# fpc.net
KiCad netlist of a schematic drawn in EAGLE
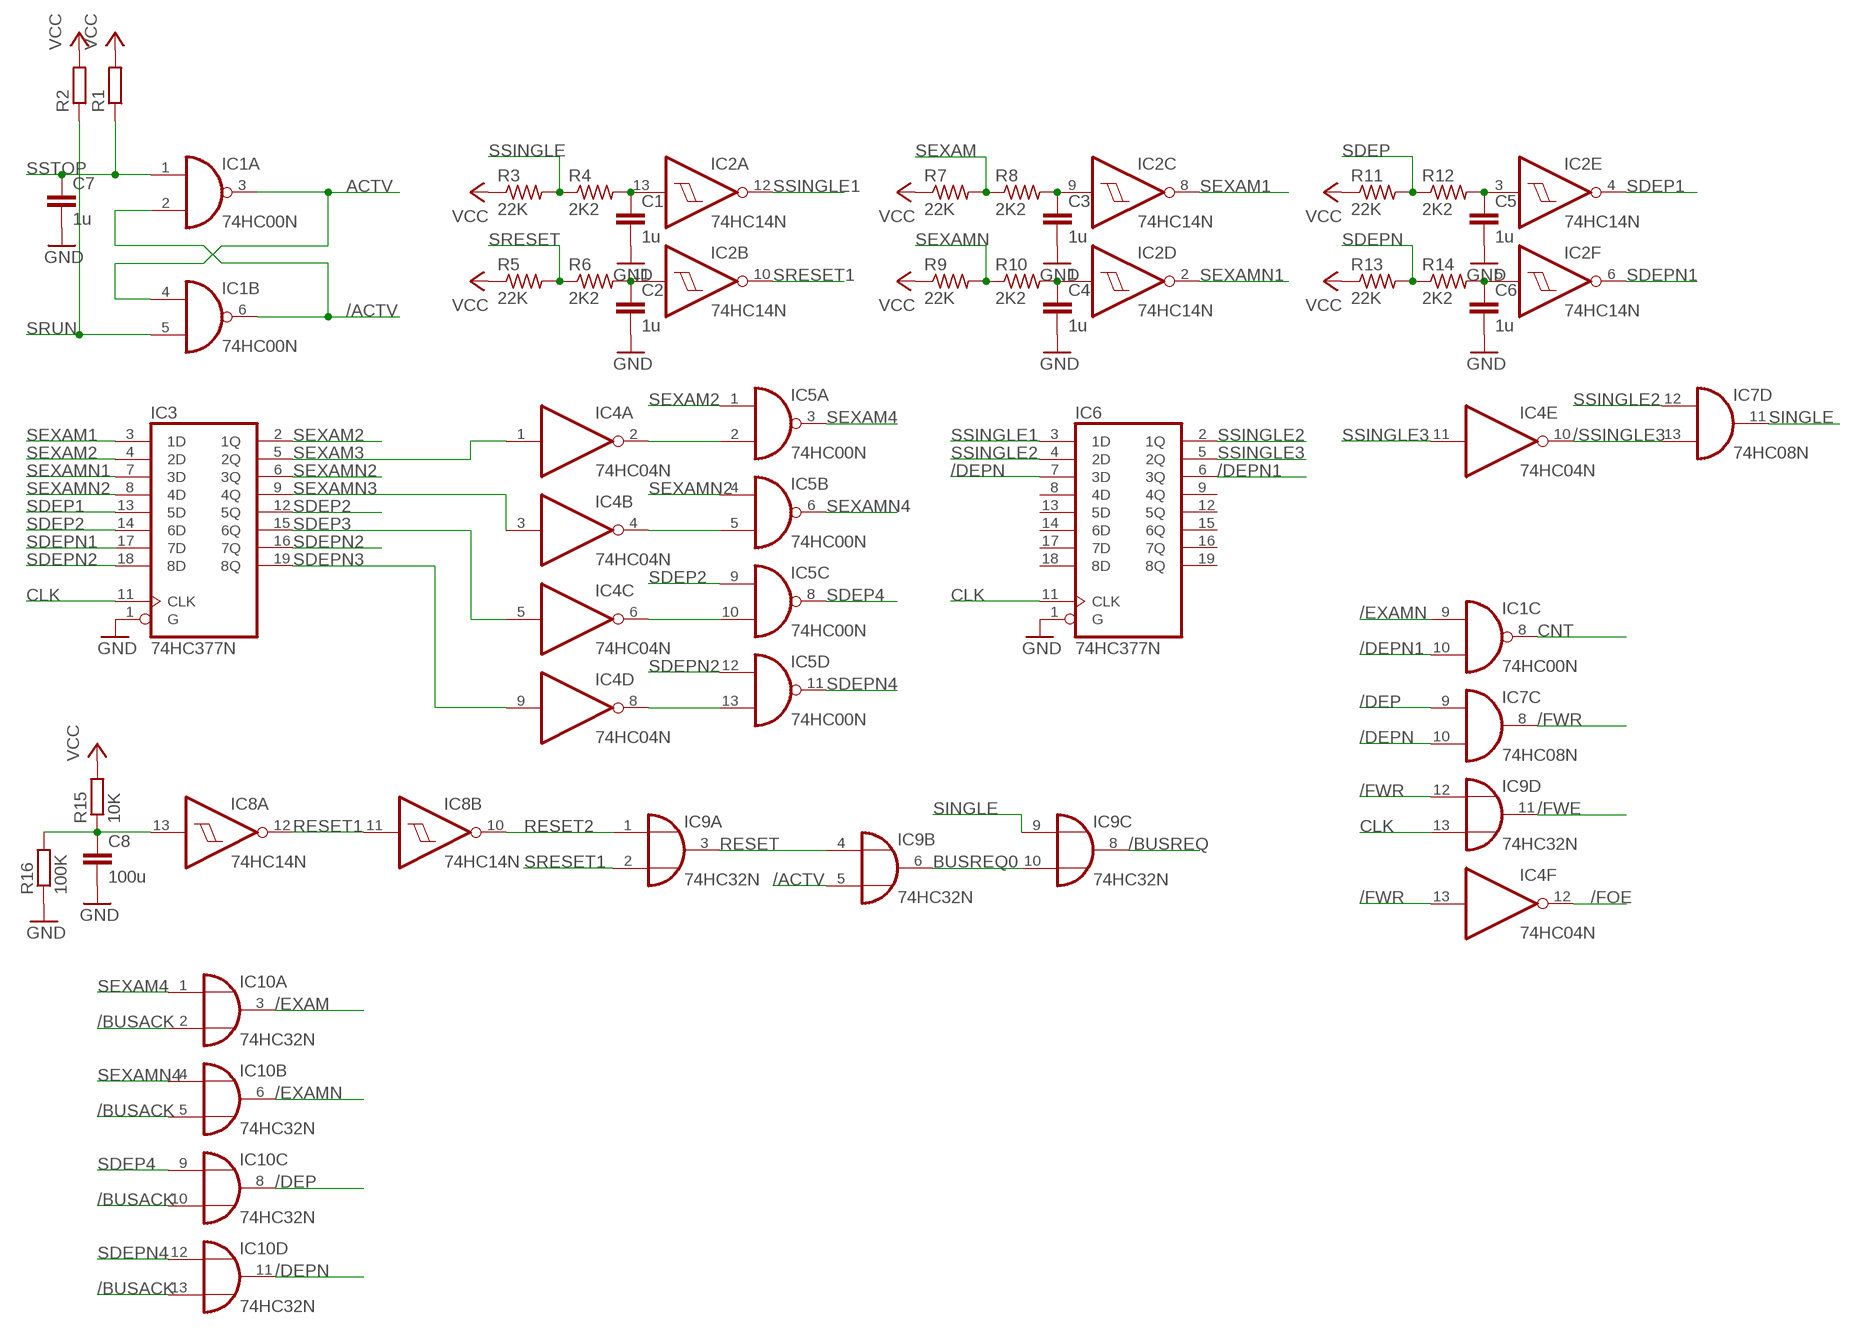
[diagram p0: schematic, sheet 1]

(export (version "E")
  (design (tool "Eeschema 10.0.6"))
  (components
    (comp (ref "C1")
      (value "1u")
      (footprint "eagle-import:C025-025X050")
      (libsource (lib "eagle-import") (part "C-EU025-025X050"))
    )
    (comp (ref "C2")
      (value "1u")
      (footprint "eagle-import:C025-025X050")
      (libsource (lib "eagle-import") (part "C-EU025-025X050"))
    )
    (comp (ref "C3")
      (value "1u")
      (footprint "eagle-import:C025-025X050")
      (libsource (lib "eagle-import") (part "C-EU025-025X050"))
    )
    (comp (ref "C4")
      (value "1u")
      (footprint "eagle-import:C025-025X050")
      (libsource (lib "eagle-import") (part "C-EU025-025X050"))
    )
    (comp (ref "C5")
      (value "1u")
      (footprint "eagle-import:C025-025X050")
      (libsource (lib "eagle-import") (part "C-EU025-025X050"))
    )
    (comp (ref "C6")
      (value "1u")
      (footprint "eagle-import:C025-025X050")
      (libsource (lib "eagle-import") (part "C-EU025-025X050"))
    )
    (comp (ref "C7")
      (value "1u")
      (footprint "eagle-import:C025-025X050")
      (libsource (lib "eagle-import") (part "C-EU025-025X050"))
    )
    (comp (ref "C8")
      (value "100u")
      (footprint "eagle-import:C025-025X050")
      (libsource (lib "eagle-import") (part "C-EU025-025X050"))
    )
    (comp (ref "IC1")
      (value "74HC00N")
      (footprint "eagle-import:DIL14")
      (libsource (lib "eagle-import") (part "7400NHC"))
    )
    (comp (ref "IC2")
      (value "74HC14N")
      (footprint "eagle-import:DIL14")
      (libsource (lib "eagle-import") (part "7414NHC"))
    )
    (comp (ref "IC3")
      (value "74HC377N")
      (footprint "eagle-import:DIL20")
      (libsource (lib "eagle-import") (part "74377NHC"))
    )
    (comp (ref "IC4")
      (value "74HC04N")
      (footprint "eagle-import:DIL14")
      (libsource (lib "eagle-import") (part "7404NHC"))
    )
    (comp (ref "IC5")
      (value "74HC00N")
      (footprint "eagle-import:DIL14")
      (libsource (lib "eagle-import") (part "7400NHC"))
    )
    (comp (ref "IC6")
      (value "74HC377N")
      (footprint "eagle-import:DIL20")
      (libsource (lib "eagle-import") (part "74377NHC"))
    )
    (comp (ref "IC7")
      (value "74HC08N")
      (footprint "eagle-import:DIL14")
      (libsource (lib "eagle-import") (part "7408NHC"))
    )
    (comp (ref "IC8")
      (value "74HC14N")
      (footprint "eagle-import:DIL14")
      (libsource (lib "eagle-import") (part "7414NHC"))
    )
    (comp (ref "IC9")
      (value "74HC32N")
      (footprint "eagle-import:DIL14")
      (libsource (lib "eagle-import") (part "7432NHC"))
    )
    (comp (ref "IC10")
      (value "74HC32N")
      (footprint "eagle-import:DIL14")
      (libsource (lib "eagle-import") (part "7432NHC"))
    )
    (comp (ref "R1")
      (value "R-EU_0309/12")
      (footprint "eagle-import:0309_12")
      (libsource (lib "eagle-import") (part "R-EU_0309/12"))
    )
    (comp (ref "R2")
      (value "R-EU_0309/12")
      (footprint "eagle-import:0309_12")
      (libsource (lib "eagle-import") (part "R-EU_0309/12"))
    )
    (comp (ref "R3")
      (value "22K")
      (footprint "eagle-import:0204_7")
      (libsource (lib "eagle-import") (part "R-US_0204/7"))
    )
    (comp (ref "R4")
      (value "2K2")
      (footprint "eagle-import:0204_7")
      (libsource (lib "eagle-import") (part "R-US_0204/7"))
    )
    (comp (ref "R5")
      (value "22K")
      (footprint "eagle-import:0204_7")
      (libsource (lib "eagle-import") (part "R-US_0204/7"))
    )
    (comp (ref "R6")
      (value "2K2")
      (footprint "eagle-import:0204_7")
      (libsource (lib "eagle-import") (part "R-US_0204/7"))
    )
    (comp (ref "R7")
      (value "22K")
      (footprint "eagle-import:0204_7")
      (libsource (lib "eagle-import") (part "R-US_0204/7"))
    )
    (comp (ref "R8")
      (value "2K2")
      (footprint "eagle-import:0204_7")
      (libsource (lib "eagle-import") (part "R-US_0204/7"))
    )
    (comp (ref "R9")
      (value "22K")
      (footprint "eagle-import:0204_7")
      (libsource (lib "eagle-import") (part "R-US_0204/7"))
    )
    (comp (ref "R10")
      (value "2K2")
      (footprint "eagle-import:0204_7")
      (libsource (lib "eagle-import") (part "R-US_0204/7"))
    )
    (comp (ref "R11")
      (value "22K")
      (footprint "eagle-import:0204_7")
      (libsource (lib "eagle-import") (part "R-US_0204/7"))
    )
    (comp (ref "R12")
      (value "2K2")
      (footprint "eagle-import:0204_7")
      (libsource (lib "eagle-import") (part "R-US_0204/7"))
    )
    (comp (ref "R13")
      (value "22K")
      (footprint "eagle-import:0204_7")
      (libsource (lib "eagle-import") (part "R-US_0204/7"))
    )
    (comp (ref "R14")
      (value "2K2")
      (footprint "eagle-import:0204_7")
      (libsource (lib "eagle-import") (part "R-US_0204/7"))
    )
    (comp (ref "R15")
      (value "10K")
      (footprint "eagle-import:0309_12")
      (libsource (lib "eagle-import") (part "R-EU_0309/12"))
    )
    (comp (ref "R16")
      (value "100K")
      (footprint "eagle-import:0309_12")
      (libsource (lib "eagle-import") (part "R-EU_0309/12"))
    )
  )
  (nets
    (net (code "1") (name "/ACTV") (class "Default")
      (node (ref "IC1") (pin "3") (pinfunction "O_3") (pintype "output"))
      (node (ref "IC1") (pin "4") (pinfunction "I0_4") (pintype "input"))
    )
    (net (code "2") (name "/BUSREQ0") (class "Default")
      (node (ref "IC9") (pin "10") (pinfunction "I1_10") (pintype "input"))
      (node (ref "IC9") (pin "6") (pinfunction "O_6") (pintype "output"))
    )
    (net (code "3") (name "/CLK") (class "Default")
      (node (ref "IC3") (pin "11") (pinfunction "CLK_11") (pintype "input"))
      (node (ref "IC6") (pin "11") (pinfunction "CLK_11") (pintype "input"))
      (node (ref "IC9") (pin "13") (pinfunction "I1_13") (pintype "input"))
    )
    (net (code "4") (name "/CNT") (class "Default")
      (node (ref "IC1") (pin "8") (pinfunction "O_8") (pintype "output"))
    )
    (net (code "5") (name "/RESET") (class "Default")
      (node (ref "IC9") (pin "3") (pinfunction "O_3") (pintype "output"))
      (node (ref "IC9") (pin "4") (pinfunction "I0_4") (pintype "input"))
    )
    (net (code "6") (name "/RESET1") (class "Default")
      (node (ref "IC8") (pin "11") (pinfunction "I_11") (pintype "input"))
      (node (ref "IC8") (pin "12") (pinfunction "O_12") (pintype "output"))
    )
    (net (code "7") (name "/RESET2") (class "Default")
      (node (ref "IC8") (pin "10") (pinfunction "O_10") (pintype "output"))
      (node (ref "IC9") (pin "1") (pinfunction "I0_1") (pintype "input"))
    )
    (net (code "8") (name "/SDEP") (class "Default")
      (node (ref "R11") (pin "2") (pinfunction "2_2") (pintype "passive"))
      (node (ref "R12") (pin "1") (pinfunction "1_1") (pintype "passive"))
    )
    (net (code "9") (name "/SDEP1") (class "Default")
      (node (ref "IC2") (pin "4") (pinfunction "O_4") (pintype "output"))
      (node (ref "IC3") (pin "13") (pinfunction "5D_13") (pintype "input"))
    )
    (net (code "10") (name "/SDEP2") (class "Default")
      (node (ref "IC3") (pin "12") (pinfunction "5Q_12") (pintype "output"))
      (node (ref "IC3") (pin "14") (pinfunction "6D_14") (pintype "input"))
      (node (ref "IC5") (pin "9") (pinfunction "I0_9") (pintype "input"))
    )
    (net (code "11") (name "/SDEP3") (class "Default")
      (node (ref "IC3") (pin "15") (pinfunction "6Q_15") (pintype "output"))
      (node (ref "IC4") (pin "5") (pinfunction "I_5") (pintype "input"))
    )
    (net (code "12") (name "/SDEP4") (class "Default")
      (node (ref "IC10") (pin "9") (pinfunction "I0_9") (pintype "input"))
      (node (ref "IC5") (pin "8") (pinfunction "O_8") (pintype "output"))
    )
    (net (code "13") (name "/SDEPN") (class "Default")
      (node (ref "R13") (pin "2") (pinfunction "2_2") (pintype "passive"))
      (node (ref "R14") (pin "1") (pinfunction "1_1") (pintype "passive"))
    )
    (net (code "14") (name "/SDEPN1") (class "Default")
      (node (ref "IC2") (pin "6") (pinfunction "O_6") (pintype "output"))
      (node (ref "IC3") (pin "17") (pinfunction "7D_17") (pintype "input"))
    )
    (net (code "15") (name "/SDEPN2") (class "Default")
      (node (ref "IC3") (pin "16") (pinfunction "7Q_16") (pintype "output"))
      (node (ref "IC3") (pin "18") (pinfunction "8D_18") (pintype "input"))
      (node (ref "IC5") (pin "12") (pinfunction "I0_12") (pintype "input"))
    )
    (net (code "16") (name "/SDEPN3") (class "Default")
      (node (ref "IC3") (pin "19") (pinfunction "8Q_19") (pintype "output"))
      (node (ref "IC4") (pin "9") (pinfunction "I_9") (pintype "input"))
    )
    (net (code "17") (name "/SDEPN4") (class "Default")
      (node (ref "IC10") (pin "12") (pinfunction "I0_12") (pintype "input"))
      (node (ref "IC5") (pin "11") (pinfunction "O_11") (pintype "output"))
    )
    (net (code "18") (name "/SEXAM") (class "Default")
      (node (ref "R7") (pin "2") (pinfunction "2_2") (pintype "passive"))
      (node (ref "R8") (pin "1") (pinfunction "1_1") (pintype "passive"))
    )
    (net (code "19") (name "/SEXAM1") (class "Default")
      (node (ref "IC2") (pin "8") (pinfunction "O_8") (pintype "output"))
      (node (ref "IC3") (pin "3") (pinfunction "1D_3") (pintype "input"))
    )
    (net (code "20") (name "/SEXAM2") (class "Default")
      (node (ref "IC3") (pin "2") (pinfunction "1Q_2") (pintype "output"))
      (node (ref "IC3") (pin "4") (pinfunction "2D_4") (pintype "input"))
      (node (ref "IC5") (pin "1") (pinfunction "I0_1") (pintype "input"))
    )
    (net (code "21") (name "/SEXAM3") (class "Default")
      (node (ref "IC3") (pin "5") (pinfunction "2Q_5") (pintype "output"))
      (node (ref "IC4") (pin "1") (pinfunction "I_1") (pintype "input"))
    )
    (net (code "22") (name "/SEXAM4") (class "Default")
      (node (ref "IC10") (pin "1") (pinfunction "I0_1") (pintype "input"))
      (node (ref "IC5") (pin "3") (pinfunction "O_3") (pintype "output"))
    )
    (net (code "23") (name "/SEXAMN") (class "Default")
      (node (ref "R10") (pin "1") (pinfunction "1_1") (pintype "passive"))
      (node (ref "R9") (pin "2") (pinfunction "2_2") (pintype "passive"))
    )
    (net (code "24") (name "/SEXAMN1") (class "Default")
      (node (ref "IC2") (pin "2") (pinfunction "O_2") (pintype "output"))
      (node (ref "IC3") (pin "7") (pinfunction "3D_7") (pintype "input"))
    )
    (net (code "25") (name "/SEXAMN2") (class "Default")
      (node (ref "IC3") (pin "6") (pinfunction "3Q_6") (pintype "output"))
      (node (ref "IC3") (pin "8") (pinfunction "4D_8") (pintype "input"))
      (node (ref "IC5") (pin "4") (pinfunction "I0_4") (pintype "input"))
    )
    (net (code "26") (name "/SEXAMN3") (class "Default")
      (node (ref "IC3") (pin "9") (pinfunction "4Q_9") (pintype "output"))
      (node (ref "IC4") (pin "3") (pinfunction "I_3") (pintype "input"))
    )
    (net (code "27") (name "/SEXAMN4") (class "Default")
      (node (ref "IC10") (pin "4") (pinfunction "I0_4") (pintype "input"))
      (node (ref "IC5") (pin "6") (pinfunction "O_6") (pintype "output"))
    )
    (net (code "28") (name "/SINGLE") (class "Default")
      (node (ref "IC7") (pin "11") (pinfunction "O_11") (pintype "output"))
      (node (ref "IC9") (pin "9") (pinfunction "I0_9") (pintype "input"))
    )
    (net (code "29") (name "/SRESET") (class "Default")
      (node (ref "R5") (pin "2") (pinfunction "2_2") (pintype "passive"))
      (node (ref "R6") (pin "1") (pinfunction "1_1") (pintype "passive"))
    )
    (net (code "30") (name "/SRESET1") (class "Default")
      (node (ref "IC2") (pin "10") (pinfunction "O_10") (pintype "output"))
      (node (ref "IC9") (pin "2") (pinfunction "I1_2") (pintype "input"))
    )
    (net (code "31") (name "/SRUN") (class "Default")
      (node (ref "IC1") (pin "5") (pinfunction "I1_5") (pintype "input"))
      (node (ref "R2") (pin "1") (pinfunction "1_1") (pintype "passive"))
    )
    (net (code "32") (name "/SSINGLE") (class "Default")
      (node (ref "R3") (pin "2") (pinfunction "2_2") (pintype "passive"))
      (node (ref "R4") (pin "1") (pinfunction "1_1") (pintype "passive"))
    )
    (net (code "33") (name "/SSINGLE1") (class "Default")
      (node (ref "IC2") (pin "12") (pinfunction "O_12") (pintype "output"))
      (node (ref "IC6") (pin "3") (pinfunction "1D_3") (pintype "input"))
    )
    (net (code "34") (name "/SSINGLE2") (class "Default")
      (node (ref "IC6") (pin "2") (pinfunction "1Q_2") (pintype "output"))
      (node (ref "IC6") (pin "4") (pinfunction "2D_4") (pintype "input"))
      (node (ref "IC7") (pin "12") (pinfunction "I0_12") (pintype "input"))
    )
    (net (code "35") (name "/SSINGLE3") (class "Default")
      (node (ref "IC4") (pin "11") (pinfunction "I_11") (pintype "input"))
      (node (ref "IC6") (pin "5") (pinfunction "2Q_5") (pintype "output"))
    )
    (net (code "36") (name "/SSTOP") (class "Default")
      (node (ref "C7") (pin "1") (pinfunction "1_1") (pintype "passive"))
      (node (ref "IC1") (pin "1") (pinfunction "I0_1") (pintype "input"))
      (node (ref "R1") (pin "1") (pinfunction "1_1") (pintype "passive"))
    )
    (net (code "37") (name "/{slash}ACTV") (class "Default")
      (node (ref "IC1") (pin "2") (pinfunction "I1_2") (pintype "input"))
      (node (ref "IC1") (pin "6") (pinfunction "O_6") (pintype "output"))
      (node (ref "IC9") (pin "5") (pinfunction "I1_5") (pintype "input"))
    )
    (net (code "38") (name "/{slash}BUSACK") (class "Default")
      (node (ref "IC10") (pin "10") (pinfunction "I1_10") (pintype "input"))
      (node (ref "IC10") (pin "13") (pinfunction "I1_13") (pintype "input"))
      (node (ref "IC10") (pin "2") (pinfunction "I1_2") (pintype "input"))
      (node (ref "IC10") (pin "5") (pinfunction "I1_5") (pintype "input"))
    )
    (net (code "39") (name "/{slash}BUSREQ") (class "Default")
      (node (ref "IC9") (pin "8") (pinfunction "O_8") (pintype "output"))
    )
    (net (code "40") (name "/{slash}DEP") (class "Default")
      (node (ref "IC10") (pin "8") (pinfunction "O_8") (pintype "output"))
      (node (ref "IC7") (pin "9") (pinfunction "I0_9") (pintype "input"))
    )
    (net (code "41") (name "/{slash}DEPN") (class "Default")
      (node (ref "IC10") (pin "11") (pinfunction "O_11") (pintype "output"))
      (node (ref "IC6") (pin "7") (pinfunction "3D_7") (pintype "input"))
      (node (ref "IC7") (pin "10") (pinfunction "I1_10") (pintype "input"))
    )
    (net (code "42") (name "/{slash}DEPN1") (class "Default")
      (node (ref "IC1") (pin "10") (pinfunction "I1_10") (pintype "input"))
      (node (ref "IC6") (pin "6") (pinfunction "3Q_6") (pintype "output"))
    )
    (net (code "43") (name "/{slash}EXAM") (class "Default")
      (node (ref "IC10") (pin "3") (pinfunction "O_3") (pintype "output"))
    )
    (net (code "44") (name "/{slash}EXAMN") (class "Default")
      (node (ref "IC1") (pin "9") (pinfunction "I0_9") (pintype "input"))
      (node (ref "IC10") (pin "6") (pinfunction "O_6") (pintype "output"))
    )
    (net (code "45") (name "/{slash}FOE") (class "Default")
      (node (ref "IC4") (pin "12") (pinfunction "O_12") (pintype "output"))
    )
    (net (code "46") (name "/{slash}FWE") (class "Default")
      (node (ref "IC9") (pin "11") (pinfunction "O_11") (pintype "output"))
    )
    (net (code "47") (name "/{slash}FWR") (class "Default")
      (node (ref "IC4") (pin "13") (pinfunction "I_13") (pintype "input"))
      (node (ref "IC7") (pin "8") (pinfunction "O_8") (pintype "output"))
      (node (ref "IC9") (pin "12") (pinfunction "I0_12") (pintype "input"))
    )
    (net (code "48") (name "/{slash}SSINGLE3") (class "Default")
      (node (ref "IC4") (pin "10") (pinfunction "O_10") (pintype "output"))
      (node (ref "IC4") (pin "2") (pinfunction "O_2") (pintype "output"))
      (node (ref "IC5") (pin "2") (pinfunction "I1_2") (pintype "input"))
      (node (ref "IC7") (pin "13") (pinfunction "I1_13") (pintype "input"))
    )
    (net (code "49") (name "GND") (class "Default")
      (node (ref "C1") (pin "2") (pinfunction "2_2") (pintype "passive"))
      (node (ref "C2") (pin "2") (pinfunction "2_2") (pintype "passive"))
      (node (ref "C3") (pin "2") (pinfunction "2_2") (pintype "passive"))
      (node (ref "C4") (pin "2") (pinfunction "2_2") (pintype "passive"))
      (node (ref "C5") (pin "2") (pinfunction "2_2") (pintype "passive"))
      (node (ref "C6") (pin "2") (pinfunction "2_2") (pintype "passive"))
      (node (ref "C7") (pin "2") (pinfunction "2_2") (pintype "passive"))
      (node (ref "C8") (pin "2") (pinfunction "2_2") (pintype "passive"))
      (node (ref "IC3") (pin "1") (pinfunction "G_1") (pintype "input"))
      (node (ref "IC6") (pin "1") (pinfunction "G_1") (pintype "input"))
      (node (ref "R16") (pin "1") (pinfunction "1_1") (pintype "passive"))
    )
    (net (code "50") (name "Net-(IC2A-I)") (class "Default")
      (node (ref "C1") (pin "1") (pinfunction "1_1") (pintype "passive"))
      (node (ref "IC2") (pin "13") (pinfunction "I_13") (pintype "input"))
      (node (ref "R4") (pin "2") (pinfunction "2_2") (pintype "passive"))
    )
    (net (code "51") (name "Net-(IC2B-I)") (class "Default")
      (node (ref "C2") (pin "1") (pinfunction "1_1") (pintype "passive"))
      (node (ref "IC2") (pin "11") (pinfunction "I_11") (pintype "input"))
      (node (ref "R6") (pin "2") (pinfunction "2_2") (pintype "passive"))
    )
    (net (code "52") (name "Net-(IC2C-I)") (class "Default")
      (node (ref "C3") (pin "1") (pinfunction "1_1") (pintype "passive"))
      (node (ref "IC2") (pin "9") (pinfunction "I_9") (pintype "input"))
      (node (ref "R8") (pin "2") (pinfunction "2_2") (pintype "passive"))
    )
    (net (code "53") (name "Net-(IC2D-I)") (class "Default")
      (node (ref "C4") (pin "1") (pinfunction "1_1") (pintype "passive"))
      (node (ref "IC2") (pin "1") (pinfunction "I_1") (pintype "input"))
      (node (ref "R10") (pin "2") (pinfunction "2_2") (pintype "passive"))
    )
    (net (code "54") (name "Net-(IC2E-I)") (class "Default")
      (node (ref "C5") (pin "1") (pinfunction "1_1") (pintype "passive"))
      (node (ref "IC2") (pin "3") (pinfunction "I_3") (pintype "input"))
      (node (ref "R12") (pin "2") (pinfunction "2_2") (pintype "passive"))
    )
    (net (code "55") (name "Net-(IC2F-I)") (class "Default")
      (node (ref "C6") (pin "1") (pinfunction "1_1") (pintype "passive"))
      (node (ref "IC2") (pin "5") (pinfunction "I_5") (pintype "input"))
      (node (ref "R14") (pin "2") (pinfunction "2_2") (pintype "passive"))
    )
    (net (code "56") (name "Net-(IC4B-O)") (class "Default")
      (node (ref "IC4") (pin "4") (pinfunction "O_4") (pintype "output"))
      (node (ref "IC5") (pin "5") (pinfunction "I1_5") (pintype "input"))
    )
    (net (code "57") (name "Net-(IC4C-O)") (class "Default")
      (node (ref "IC4") (pin "6") (pinfunction "O_6") (pintype "output"))
      (node (ref "IC5") (pin "10") (pinfunction "I1_10") (pintype "input"))
    )
    (net (code "58") (name "Net-(IC4D-O)") (class "Default")
      (node (ref "IC4") (pin "8") (pinfunction "O_8") (pintype "output"))
      (node (ref "IC5") (pin "13") (pinfunction "I1_13") (pintype "input"))
    )
    (net (code "59") (name "Net-(IC8A-I)") (class "Default")
      (node (ref "C8") (pin "1") (pinfunction "1_1") (pintype "passive"))
      (node (ref "IC8") (pin "13") (pinfunction "I_13") (pintype "input"))
      (node (ref "R15") (pin "1") (pinfunction "1_1") (pintype "passive"))
      (node (ref "R16") (pin "2") (pinfunction "2_2") (pintype "passive"))
    )
    (net (code "60") (name "VCC") (class "Default")
      (node (ref "R1") (pin "2") (pinfunction "2_2") (pintype "passive"))
      (node (ref "R11") (pin "1") (pinfunction "1_1") (pintype "passive"))
      (node (ref "R13") (pin "1") (pinfunction "1_1") (pintype "passive"))
      (node (ref "R15") (pin "2") (pinfunction "2_2") (pintype "passive"))
      (node (ref "R2") (pin "2") (pinfunction "2_2") (pintype "passive"))
      (node (ref "R3") (pin "1") (pinfunction "1_1") (pintype "passive"))
      (node (ref "R5") (pin "1") (pinfunction "1_1") (pintype "passive"))
      (node (ref "R7") (pin "1") (pinfunction "1_1") (pintype "passive"))
      (node (ref "R9") (pin "1") (pinfunction "1_1") (pintype "passive"))
    )
    (net (code "61") (name "unconnected-(IC6A-4D-Pad8)") (class "Default")
      (node (ref "IC6") (pin "8") (pinfunction "4D_8") (pintype "input"))
    )
    (net (code "62") (name "unconnected-(IC6A-4Q-Pad9)") (class "Default")
      (node (ref "IC6") (pin "9") (pinfunction "4Q_9") (pintype "output"))
    )
    (net (code "63") (name "unconnected-(IC6A-5D-Pad13)") (class "Default")
      (node (ref "IC6") (pin "13") (pinfunction "5D_13") (pintype "input"))
    )
    (net (code "64") (name "unconnected-(IC6A-5Q-Pad12)") (class "Default")
      (node (ref "IC6") (pin "12") (pinfunction "5Q_12") (pintype "output"))
    )
    (net (code "65") (name "unconnected-(IC6A-6D-Pad14)") (class "Default")
      (node (ref "IC6") (pin "14") (pinfunction "6D_14") (pintype "input"))
    )
    (net (code "66") (name "unconnected-(IC6A-6Q-Pad15)") (class "Default")
      (node (ref "IC6") (pin "15") (pinfunction "6Q_15") (pintype "output"))
    )
    (net (code "67") (name "unconnected-(IC6A-7D-Pad17)") (class "Default")
      (node (ref "IC6") (pin "17") (pinfunction "7D_17") (pintype "input"))
    )
    (net (code "68") (name "unconnected-(IC6A-7Q-Pad16)") (class "Default")
      (node (ref "IC6") (pin "16") (pinfunction "7Q_16") (pintype "output"))
    )
    (net (code "69") (name "unconnected-(IC6A-8D-Pad18)") (class "Default")
      (node (ref "IC6") (pin "18") (pinfunction "8D_18") (pintype "input"))
    )
    (net (code "70") (name "unconnected-(IC6A-8Q-Pad19)") (class "Default")
      (node (ref "IC6") (pin "19") (pinfunction "8Q_19") (pintype "output"))
    )
  )
)
